# display_schematic.net
KiCad netlist of a schematic drawn in Altium Designer
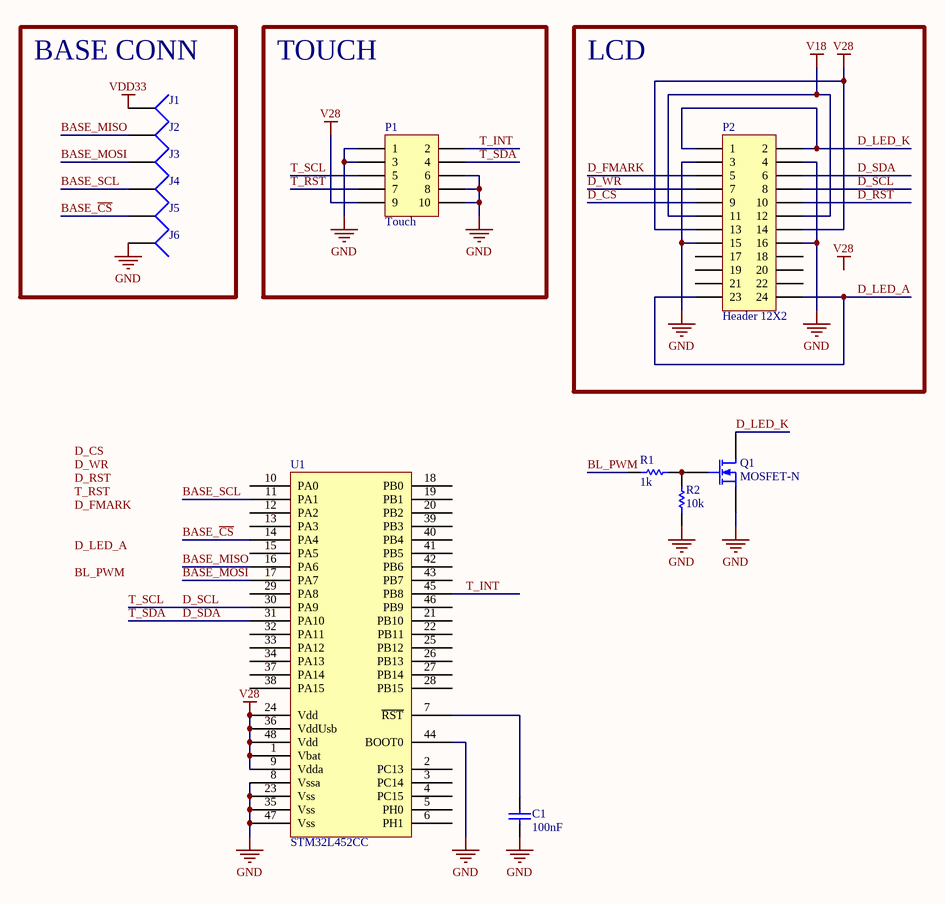
[diagram p0: display_schematic.SchDoc]

(export (version "E")
  (design (tool "Eeschema 10.0.6"))
  (components
    (comp (ref "C1")
      (value "100nF")
      (footprint "RAD-0.3")
      (description "Capacitor")
      (fields (field (name "PUBLISHER") "Altium Limited"))
      (libsource (lib "Miscellaneous Devices") (part "Cap"))
    )
    (comp (ref "J1")
      (value "Socket")
      (footprint "PIN1")
      (fields (field (name "PUBLISHER") "Altium Limited"))
      (libsource (lib "Miscellaneous Connectors") (part "Socket"))
    )
    (comp (ref "J2")
      (value "Socket")
      (footprint "PIN1")
      (fields (field (name "PUBLISHER") "Altium Limited"))
      (libsource (lib "Miscellaneous Connectors") (part "Socket"))
    )
    (comp (ref "J3")
      (value "Socket")
      (footprint "PIN1")
      (fields (field (name "PUBLISHER") "Altium Limited"))
      (libsource (lib "Miscellaneous Connectors") (part "Socket"))
    )
    (comp (ref "J4")
      (value "Socket")
      (footprint "PIN1")
      (fields (field (name "PUBLISHER") "Altium Limited"))
      (libsource (lib "Miscellaneous Connectors") (part "Socket"))
    )
    (comp (ref "J5")
      (value "Socket")
      (footprint "PIN1")
      (fields (field (name "PUBLISHER") "Altium Limited"))
      (libsource (lib "Miscellaneous Connectors") (part "Socket"))
    )
    (comp (ref "J6")
      (value "Socket")
      (footprint "PIN1")
      (fields (field (name "PUBLISHER") "Altium Limited"))
      (libsource (lib "Miscellaneous Connectors") (part "Socket"))
    )
    (comp (ref "P1")
      (value "Touch")
      (footprint "HRS_DF37C-10DP-0.4V(51)")
      (description "Header, 5-Pin, Dual row")
      (fields (field (name "PUBLISHER") "Altium Limited"))
      (libsource (lib "Miscellaneous Connectors") (part "Header 5X2"))
    )
    (comp (ref "P2")
      (value "Header 12X2")
      (footprint "HRS_DF37C-24DP-0.4V(51)")
      (description "Header, 12-Pin, Dual row")
      (fields (field (name "PUBLISHER") "Altium Limited"))
      (libsource (lib "Miscellaneous Connectors") (part "Header 12X2"))
    )
    (comp (ref "Q1")
      (value "MOSFET-N")
      (footprint "E3")
      (description "N-Channel MOSFET")
      (fields (field (name "PUBLISHER") "Altium Limited"))
      (libsource (lib "Miscellaneous Devices") (part "MOSFET-N"))
    )
    (comp (ref "R1")
      (value "1k")
      (footprint "AXIAL-0.3")
      (description "Resistor")
      (fields (field (name "PUBLISHER") "Altium Limited"))
      (libsource (lib "Miscellaneous Devices") (part "Res1"))
    )
    (comp (ref "R2")
      (value "10k")
      (footprint "AXIAL-0.3")
      (description "Resistor")
      (fields (field (name "PUBLISHER") "Altium Limited"))
      (libsource (lib "Miscellaneous Devices") (part "Res1"))
    )
    (comp (ref "U1") (value "STM32L452CC") (libsource (lib "sch_lib") (part "STN32L452CC")))
  )
  (nets
    (net (code "1") (name "/BASE_MISO") (class "Default")
      (node (ref "J2") (pin "1") (pinfunction "1_1") (pintype "passive"))
      (node (ref "U1") (pin "16") (pinfunction "PA6_16") (pintype "passive"))
    )
    (net (code "2") (name "/BASE_MOSI") (class "Default")
      (node (ref "J3") (pin "1") (pinfunction "1_1") (pintype "passive"))
      (node (ref "U1") (pin "17") (pinfunction "PA7_17") (pintype "passive"))
    )
    (net (code "3") (name "/BASE_SCL") (class "Default")
      (node (ref "J4") (pin "1") (pinfunction "1_1") (pintype "passive"))
      (node (ref "U1") (pin "11") (pinfunction "PA1_11") (pintype "passive"))
    )
    (net (code "4") (name "/BASE_~{CS}") (class "Default")
      (node (ref "J5") (pin "1") (pinfunction "1_1") (pintype "passive"))
      (node (ref "U1") (pin "14") (pinfunction "PA4_14") (pintype "passive"))
    )
    (net (code "5") (name "/BL_PWM") (class "Default")
      (node (ref "R1") (pin "1") (pinfunction "1_1") (pintype "passive"))
    )
    (net (code "6") (name "/D_CS") (class "Default")
      (node (ref "P2") (pin "9") (pinfunction "9_9") (pintype "passive"))
    )
    (net (code "7") (name "/D_FMARK") (class "Default")
      (node (ref "P2") (pin "5") (pinfunction "5_5") (pintype "passive"))
    )
    (net (code "8") (name "/D_LED_A") (class "Default")
      (node (ref "P2") (pin "23") (pinfunction "23_23") (pintype "passive"))
      (node (ref "P2") (pin "24") (pinfunction "24_24") (pintype "passive"))
    )
    (net (code "9") (name "/D_LED_K") (class "Default")
      (node (ref "P2") (pin "1") (pinfunction "1_1") (pintype "passive"))
      (node (ref "P2") (pin "2") (pinfunction "2_2") (pintype "passive"))
      (node (ref "Q1") (pin "1") (pinfunction "D_1") (pintype "passive"))
    )
    (net (code "10") (name "/D_RST") (class "Default")
      (node (ref "P2") (pin "10") (pinfunction "10_10") (pintype "passive"))
    )
    (net (code "11") (name "/D_SCL") (class "Default")
      (node (ref "P1") (pin "5") (pinfunction "5_5") (pintype "passive"))
      (node (ref "P2") (pin "8") (pinfunction "8_8") (pintype "passive"))
      (node (ref "U1") (pin "30") (pinfunction "PA9_30") (pintype "passive"))
    )
    (net (code "12") (name "/D_SDA") (class "Default")
      (node (ref "P1") (pin "4") (pinfunction "4_4") (pintype "passive"))
      (node (ref "P2") (pin "6") (pinfunction "6_6") (pintype "passive"))
      (node (ref "U1") (pin "31") (pinfunction "PA10_31") (pintype "passive"))
    )
    (net (code "13") (name "/D_WR") (class "Default")
      (node (ref "P2") (pin "7") (pinfunction "7_7") (pintype "passive"))
    )
    (net (code "14") (name "/T_INT") (class "Default")
      (node (ref "P1") (pin "2") (pinfunction "2_2") (pintype "passive"))
      (node (ref "U1") (pin "45") (pinfunction "PB8_45") (pintype "passive"))
    )
    (net (code "15") (name "/T_RST") (class "Default")
      (node (ref "P1") (pin "7") (pinfunction "7_7") (pintype "passive"))
    )
    (net (code "16") (name "GND") (class "Default")
      (node (ref "C1") (pin "1") (pinfunction "1_1") (pintype "passive"))
      (node (ref "J6") (pin "1") (pinfunction "1_1") (pintype "passive"))
      (node (ref "P1") (pin "1") (pinfunction "1_1") (pintype "passive"))
      (node (ref "P1") (pin "10") (pinfunction "10_10") (pintype "passive"))
      (node (ref "P1") (pin "3") (pinfunction "3_3") (pintype "passive"))
      (node (ref "P1") (pin "6") (pinfunction "6_6") (pintype "passive"))
      (node (ref "P1") (pin "8") (pinfunction "8_8") (pintype "passive"))
      (node (ref "P2") (pin "15") (pinfunction "15_15") (pintype "passive"))
      (node (ref "P2") (pin "16") (pinfunction "16_16") (pintype "passive"))
      (node (ref "P2") (pin "3") (pinfunction "3_3") (pintype "passive"))
      (node (ref "P2") (pin "4") (pinfunction "4_4") (pintype "passive"))
      (node (ref "Q1") (pin "3") (pinfunction "S_3") (pintype "passive"))
      (node (ref "R2") (pin "1") (pinfunction "1_1") (pintype "passive"))
      (node (ref "U1") (pin "23") (pinfunction "Vss_23") (pintype "passive"))
      (node (ref "U1") (pin "35") (pinfunction "Vss_35") (pintype "passive"))
      (node (ref "U1") (pin "44") (pinfunction "BOOT0_44") (pintype "passive"))
      (node (ref "U1") (pin "47") (pinfunction "Vss_47") (pintype "passive"))
      (node (ref "U1") (pin "8") (pinfunction "Vssa_8") (pintype "passive"))
    )
    (net (code "17") (name "Net-(Q1-G)") (class "Default")
      (node (ref "Q1") (pin "2") (pinfunction "G_2") (pintype "passive"))
      (node (ref "R1") (pin "2") (pinfunction "2_2") (pintype "passive"))
      (node (ref "R2") (pin "2") (pinfunction "2_2") (pintype "passive"))
    )
    (net (code "18") (name "Net-(U1-~{RST})") (class "Default")
      (node (ref "C1") (pin "2") (pinfunction "2_2") (pintype "passive"))
      (node (ref "U1") (pin "7") (pinfunction "~{RST}_7") (pintype "passive"))
    )
    (net (code "19") (name "V18") (class "Default")
      (node (ref "P2") (pin "11") (pinfunction "11_11") (pintype "passive"))
      (node (ref "P2") (pin "12") (pinfunction "12_12") (pintype "passive"))
    )
    (net (code "20") (name "V28") (class "Default")
      (node (ref "P1") (pin "9") (pinfunction "9_9") (pintype "passive"))
      (node (ref "P2") (pin "13") (pinfunction "13_13") (pintype "passive"))
      (node (ref "P2") (pin "14") (pinfunction "14_14") (pintype "passive"))
      (node (ref "U1") (pin "1") (pinfunction "Vbat_1") (pintype "passive"))
      (node (ref "U1") (pin "24") (pinfunction "Vdd_24") (pintype "passive"))
      (node (ref "U1") (pin "36") (pinfunction "VddUsb_36") (pintype "passive"))
      (node (ref "U1") (pin "48") (pinfunction "Vdd_48") (pintype "passive"))
      (node (ref "U1") (pin "9") (pinfunction "Vdda_9") (pintype "passive"))
    )
    (net (code "21") (name "VDD33") (class "Default")
      (node (ref "J1") (pin "1") (pinfunction "1_1") (pintype "passive"))
    )
    (net (code "22") (name "unconnected-(P2-Pad17)") (class "Default")
      (node (ref "P2") (pin "17") (pinfunction "17_17") (pintype "passive"))
    )
    (net (code "23") (name "unconnected-(P2-Pad18)") (class "Default")
      (node (ref "P2") (pin "18") (pinfunction "18_18") (pintype "passive"))
    )
    (net (code "24") (name "unconnected-(P2-Pad19)") (class "Default")
      (node (ref "P2") (pin "19") (pinfunction "19_19") (pintype "passive"))
    )
    (net (code "25") (name "unconnected-(P2-Pad20)") (class "Default")
      (node (ref "P2") (pin "20") (pinfunction "20_20") (pintype "passive"))
    )
    (net (code "26") (name "unconnected-(P2-Pad21)") (class "Default")
      (node (ref "P2") (pin "21") (pinfunction "21_21") (pintype "passive"))
    )
    (net (code "27") (name "unconnected-(P2-Pad22)") (class "Default")
      (node (ref "P2") (pin "22") (pinfunction "22_22") (pintype "passive"))
    )
    (net (code "28") (name "unconnected-(U1-PA0-Pad10)") (class "Default")
      (node (ref "U1") (pin "10") (pinfunction "PA0_10") (pintype "passive"))
    )
    (net (code "29") (name "unconnected-(U1-PA2-Pad12)") (class "Default")
      (node (ref "U1") (pin "12") (pinfunction "PA2_12") (pintype "passive"))
    )
    (net (code "30") (name "unconnected-(U1-PA3-Pad13)") (class "Default")
      (node (ref "U1") (pin "13") (pinfunction "PA3_13") (pintype "passive"))
    )
    (net (code "31") (name "unconnected-(U1-PA5-Pad15)") (class "Default")
      (node (ref "U1") (pin "15") (pinfunction "PA5_15") (pintype "passive"))
    )
    (net (code "32") (name "unconnected-(U1-PA8-Pad29)") (class "Default")
      (node (ref "U1") (pin "29") (pinfunction "PA8_29") (pintype "passive"))
    )
    (net (code "33") (name "unconnected-(U1-PA11-Pad32)") (class "Default")
      (node (ref "U1") (pin "32") (pinfunction "PA11_32") (pintype "passive"))
    )
    (net (code "34") (name "unconnected-(U1-PA12-Pad33)") (class "Default")
      (node (ref "U1") (pin "33") (pinfunction "PA12_33") (pintype "passive"))
    )
    (net (code "35") (name "unconnected-(U1-PA13-Pad34)") (class "Default")
      (node (ref "U1") (pin "34") (pinfunction "PA13_34") (pintype "passive"))
    )
    (net (code "36") (name "unconnected-(U1-PA14-Pad37)") (class "Default")
      (node (ref "U1") (pin "37") (pinfunction "PA14_37") (pintype "passive"))
    )
    (net (code "37") (name "unconnected-(U1-PA15-Pad38)") (class "Default")
      (node (ref "U1") (pin "38") (pinfunction "PA15_38") (pintype "passive"))
    )
    (net (code "38") (name "unconnected-(U1-PB0-Pad18)") (class "Default")
      (node (ref "U1") (pin "18") (pinfunction "PB0_18") (pintype "passive"))
    )
    (net (code "39") (name "unconnected-(U1-PB1-Pad19)") (class "Default")
      (node (ref "U1") (pin "19") (pinfunction "PB1_19") (pintype "passive"))
    )
    (net (code "40") (name "unconnected-(U1-PB2-Pad20)") (class "Default")
      (node (ref "U1") (pin "20") (pinfunction "PB2_20") (pintype "passive"))
    )
    (net (code "41") (name "unconnected-(U1-PB3-Pad39)") (class "Default")
      (node (ref "U1") (pin "39") (pinfunction "PB3_39") (pintype "passive"))
    )
    (net (code "42") (name "unconnected-(U1-PB4-Pad40)") (class "Default")
      (node (ref "U1") (pin "40") (pinfunction "PB4_40") (pintype "passive"))
    )
    (net (code "43") (name "unconnected-(U1-PB5-Pad41)") (class "Default")
      (node (ref "U1") (pin "41") (pinfunction "PB5_41") (pintype "passive"))
    )
    (net (code "44") (name "unconnected-(U1-PB6-Pad42)") (class "Default")
      (node (ref "U1") (pin "42") (pinfunction "PB6_42") (pintype "passive"))
    )
    (net (code "45") (name "unconnected-(U1-PB7-Pad43)") (class "Default")
      (node (ref "U1") (pin "43") (pinfunction "PB7_43") (pintype "passive"))
    )
    (net (code "46") (name "unconnected-(U1-PB9-Pad46)") (class "Default")
      (node (ref "U1") (pin "46") (pinfunction "PB9_46") (pintype "passive"))
    )
    (net (code "47") (name "unconnected-(U1-PB10-Pad21)") (class "Default")
      (node (ref "U1") (pin "21") (pinfunction "PB10_21") (pintype "passive"))
    )
    (net (code "48") (name "unconnected-(U1-PB11-Pad22)") (class "Default")
      (node (ref "U1") (pin "22") (pinfunction "PB11_22") (pintype "passive"))
    )
    (net (code "49") (name "unconnected-(U1-PB12-Pad25)") (class "Default")
      (node (ref "U1") (pin "25") (pinfunction "PB12_25") (pintype "passive"))
    )
    (net (code "50") (name "unconnected-(U1-PB13-Pad26)") (class "Default")
      (node (ref "U1") (pin "26") (pinfunction "PB13_26") (pintype "passive"))
    )
    (net (code "51") (name "unconnected-(U1-PB14-Pad27)") (class "Default")
      (node (ref "U1") (pin "27") (pinfunction "PB14_27") (pintype "passive"))
    )
    (net (code "52") (name "unconnected-(U1-PB15-Pad28)") (class "Default")
      (node (ref "U1") (pin "28") (pinfunction "PB15_28") (pintype "passive"))
    )
    (net (code "53") (name "unconnected-(U1-PC13-Pad2)") (class "Default")
      (node (ref "U1") (pin "2") (pinfunction "PC13_2") (pintype "passive"))
    )
    (net (code "54") (name "unconnected-(U1-PC14-Pad3)") (class "Default")
      (node (ref "U1") (pin "3") (pinfunction "PC14_3") (pintype "passive"))
    )
    (net (code "55") (name "unconnected-(U1-PC15-Pad4)") (class "Default")
      (node (ref "U1") (pin "4") (pinfunction "PC15_4") (pintype "passive"))
    )
    (net (code "56") (name "unconnected-(U1-PH0-Pad5)") (class "Default")
      (node (ref "U1") (pin "5") (pinfunction "PH0_5") (pintype "passive"))
    )
    (net (code "57") (name "unconnected-(U1-PH1-Pad6)") (class "Default")
      (node (ref "U1") (pin "6") (pinfunction "PH1_6") (pintype "passive"))
    )
  )
)
